# OLED.net
KiCad netlist of a schematic drawn in Altium Designer
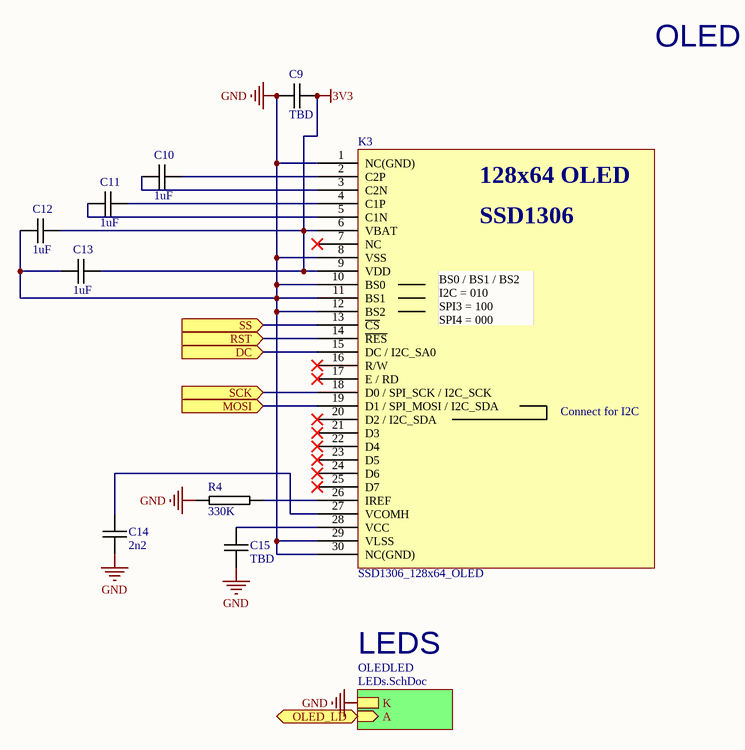
[diagram p0: OLED.SchDoc]

(export (version "E")
  (design (tool "Eeschema 10.0.6"))
  (components
    (comp (ref "C9")
      (value "TBD")
      (footprint "1210C-GENERIC")
      (description "CAPACITOR 1210 CERAMIC VALUE TO BE DETERMINED")
      (libsource (lib "RVA_Altium_Library") (part "Passives_Capacitors_1210_1210C-TBD"))
    )
    (comp (ref "C10")
      (value "1uF")
      (footprint "0603C-GENERIC")
      (description "CAPACITOR 0603 CERAMIC")
      (fields
        (field (name "MANUFACTURER PART NUMBER") "GMK107BJ105KA-T")
        (field (name "MANUFACTURER") "Taiyo Yuden")
      )
      (libsource (lib "RVA_Altium_Library") (part "0603C-1UF-35V-X5R-TAY"))
    )
    (comp (ref "C11")
      (value "1uF")
      (footprint "0603C-GENERIC")
      (description "CAPACITOR 0603 CERAMIC")
      (fields
        (field (name "MANUFACTURER PART NUMBER") "GMK107BJ105KA-T")
        (field (name "MANUFACTURER") "Taiyo Yuden")
      )
      (libsource (lib "RVA_Altium_Library") (part "0603C-1UF-35V-X5R-TAY"))
    )
    (comp (ref "C12")
      (value "1uF")
      (footprint "0603C-GENERIC")
      (description "CAPACITOR 0603 CERAMIC")
      (fields
        (field (name "MANUFACTURER PART NUMBER") "GMK107BJ105KA-T")
        (field (name "MANUFACTURER") "Taiyo Yuden")
      )
      (libsource (lib "RVA_Altium_Library") (part "0603C-1UF-35V-X5R-TAY"))
    )
    (comp (ref "C13")
      (value "1uF")
      (footprint "0603C-GENERIC")
      (description "CAPACITOR 0603 CERAMIC")
      (fields
        (field (name "MANUFACTURER PART NUMBER") "GMK107BJ105KA-T")
        (field (name "MANUFACTURER") "Taiyo Yuden")
      )
      (libsource (lib "RVA_Altium_Library") (part "0603C-1UF-35V-X5R-TAY"))
    )
    (comp (ref "C14")
      (value "2n2")
      (footprint "0603C-GENERIC")
      (description "CAPACITOR 0603 CERAMIC")
      (libsource (lib "RVA_Altium_Library") (part "0603C-2N2-50V-C0G-MUR"))
    )
    (comp (ref "C15")
      (value "TBD")
      (footprint "1210C-GENERIC")
      (description "CAPACITOR 1210 CERAMIC VALUE TO BE DETERMINED")
      (libsource (lib "RVA_Altium_Library") (part "Passives_Capacitors_1210_1210C-TBD"))
    )
    (comp (ref "K3")
      (value "SSD1306_128x64_OLED")
      (footprint "SSD1306_128x64_OLED")
      (description "SSD1306 OLED 128x64")
      (libsource (lib "RVA_Altium_Library") (part "SSD1306_128x64_OLED"))
    )
    (comp (ref "R4")
      (value "330K")
      (footprint "0603R-330K")
      (description "GENERIC RESISTOR 0603")
      (fields
        (field (name "MANUFACTURER") "Stackpole Electronics Inc")
        (field (name "MANUFACTURER PART NUMBER") "RMCF 1/16 330K 1% R")
      )
      (libsource (lib "RVA_Altium_Library") (part "0603R-330K"))
    )
  )
  (nets
    (net (code "1") (name "/DC") (class "Default")
      (node (ref "K3") (pin "15") (pinfunction "DC_/_I2C_SA0_15") (pintype "passive"))
    )
    (net (code "2") (name "/MOSI") (class "Default")
      (node (ref "K3") (pin "19") (pinfunction "D1_/_SPI_MOSI_/_I2C_SDA_19") (pintype "passive"))
    )
    (net (code "4") (name "/RST") (class "Default")
      (node (ref "K3") (pin "14") (pinfunction "~{RES}_14") (pintype "passive"))
    )
    (net (code "5") (name "/SCK") (class "Default")
      (node (ref "K3") (pin "18") (pinfunction "D0_/_SPI_SCK_/_I2C_SCK_18") (pintype "passive"))
    )
    (net (code "6") (name "/SS") (class "Default")
      (node (ref "K3") (pin "13") (pinfunction "~{CS}_13") (pintype "passive"))
    )
    (net (code "7") (name "3V3") (class "Default")
      (node (ref "C12") (pin "2") (pintype "passive"))
      (node (ref "C13") (pin "2") (pintype "passive"))
      (node (ref "C9") (pin "2") (pintype "passive"))
      (node (ref "K3") (pin "6") (pinfunction "VBAT_6") (pintype "passive"))
      (node (ref "K3") (pin "9") (pinfunction "VDD_9") (pintype "passive"))
    )
    (net (code "8") (name "GND") (class "Default")
      (node (ref "C12") (pin "1") (pintype "passive"))
      (node (ref "C13") (pin "1") (pintype "passive"))
      (node (ref "C14") (pin "2") (pintype "passive"))
      (node (ref "C15") (pin "1") (pintype "passive"))
      (node (ref "C9") (pin "1") (pintype "passive"))
      (node (ref "K3") (pin "1") (pinfunction "NC(GND)_1") (pintype "passive"))
      (node (ref "K3") (pin "10") (pinfunction "BS0_10") (pintype "passive"))
      (node (ref "K3") (pin "11") (pinfunction "BS1_11") (pintype "passive"))
      (node (ref "K3") (pin "12") (pinfunction "BS2_12") (pintype "passive"))
      (node (ref "K3") (pin "29") (pinfunction "VLSS_29") (pintype "passive"))
      (node (ref "K3") (pin "30") (pinfunction "NC(GND)_30") (pintype "passive"))
      (node (ref "K3") (pin "8") (pinfunction "VSS_8") (pintype "passive"))
      (node (ref "R4") (pin "1") (pintype "passive"))
    )
    (net (code "9") (name "Net-(K3-C1N)") (class "Default")
      (node (ref "C11") (pin "1") (pintype "passive"))
      (node (ref "K3") (pin "5") (pinfunction "C1N_5") (pintype "passive"))
    )
    (net (code "10") (name "Net-(K3-C1P)") (class "Default")
      (node (ref "C11") (pin "2") (pintype "passive"))
      (node (ref "K3") (pin "4") (pinfunction "C1P_4") (pintype "passive"))
    )
    (net (code "11") (name "Net-(K3-C2N)") (class "Default")
      (node (ref "C10") (pin "1") (pintype "passive"))
      (node (ref "K3") (pin "3") (pinfunction "C2N_3") (pintype "passive"))
    )
    (net (code "12") (name "Net-(K3-C2P)") (class "Default")
      (node (ref "C10") (pin "2") (pintype "passive"))
      (node (ref "K3") (pin "2") (pinfunction "C2P_2") (pintype "passive"))
    )
    (net (code "13") (name "Net-(K3-IREF)") (class "Default")
      (node (ref "K3") (pin "26") (pinfunction "IREF_26") (pintype "passive"))
      (node (ref "R4") (pin "2") (pintype "passive"))
    )
    (net (code "14") (name "Net-(K3-VCC)") (class "Default")
      (node (ref "C15") (pin "2") (pintype "passive"))
      (node (ref "K3") (pin "28") (pinfunction "VCC_28") (pintype "passive"))
    )
    (net (code "15") (name "Net-(K3-VCOMH)") (class "Default")
      (node (ref "C14") (pin "1") (pintype "passive"))
      (node (ref "K3") (pin "27") (pinfunction "VCOMH_27") (pintype "passive"))
    )
    (net (code "16") (name "unconnected-(K3-D2_{slash}_I2C_SDA-Pad20)") (class "Default")
      (node (ref "K3") (pin "20") (pinfunction "D2_/_I2C_SDA_20") (pintype "passive+no_connect"))
    )
    (net (code "17") (name "unconnected-(K3-D3-Pad21)") (class "Default")
      (node (ref "K3") (pin "21") (pinfunction "D3_21") (pintype "passive+no_connect"))
    )
    (net (code "18") (name "unconnected-(K3-D4-Pad22)") (class "Default")
      (node (ref "K3") (pin "22") (pinfunction "D4_22") (pintype "passive+no_connect"))
    )
    (net (code "19") (name "unconnected-(K3-D5-Pad23)") (class "Default")
      (node (ref "K3") (pin "23") (pinfunction "D5_23") (pintype "passive+no_connect"))
    )
    (net (code "20") (name "unconnected-(K3-D6-Pad24)") (class "Default")
      (node (ref "K3") (pin "24") (pinfunction "D6_24") (pintype "passive+no_connect"))
    )
    (net (code "21") (name "unconnected-(K3-D7-Pad25)") (class "Default")
      (node (ref "K3") (pin "25") (pinfunction "D7_25") (pintype "passive+no_connect"))
    )
    (net (code "22") (name "unconnected-(K3-E_{slash}_RD-Pad17)") (class "Default")
      (node (ref "K3") (pin "17") (pinfunction "E_/_RD_17") (pintype "passive+no_connect"))
    )
    (net (code "23") (name "unconnected-(K3-NC-Pad7)") (class "Default")
      (node (ref "K3") (pin "7") (pinfunction "NC_7") (pintype "passive+no_connect"))
    )
    (net (code "24") (name "unconnected-(K3-R{slash}W-Pad16)") (class "Default")
      (node (ref "K3") (pin "16") (pinfunction "R/W_16") (pintype "passive+no_connect"))
    )
  )
)
